# MD070B_POWER_AND_CONNECTORS.net
KiCad netlist of a schematic drawn in Altium Designer
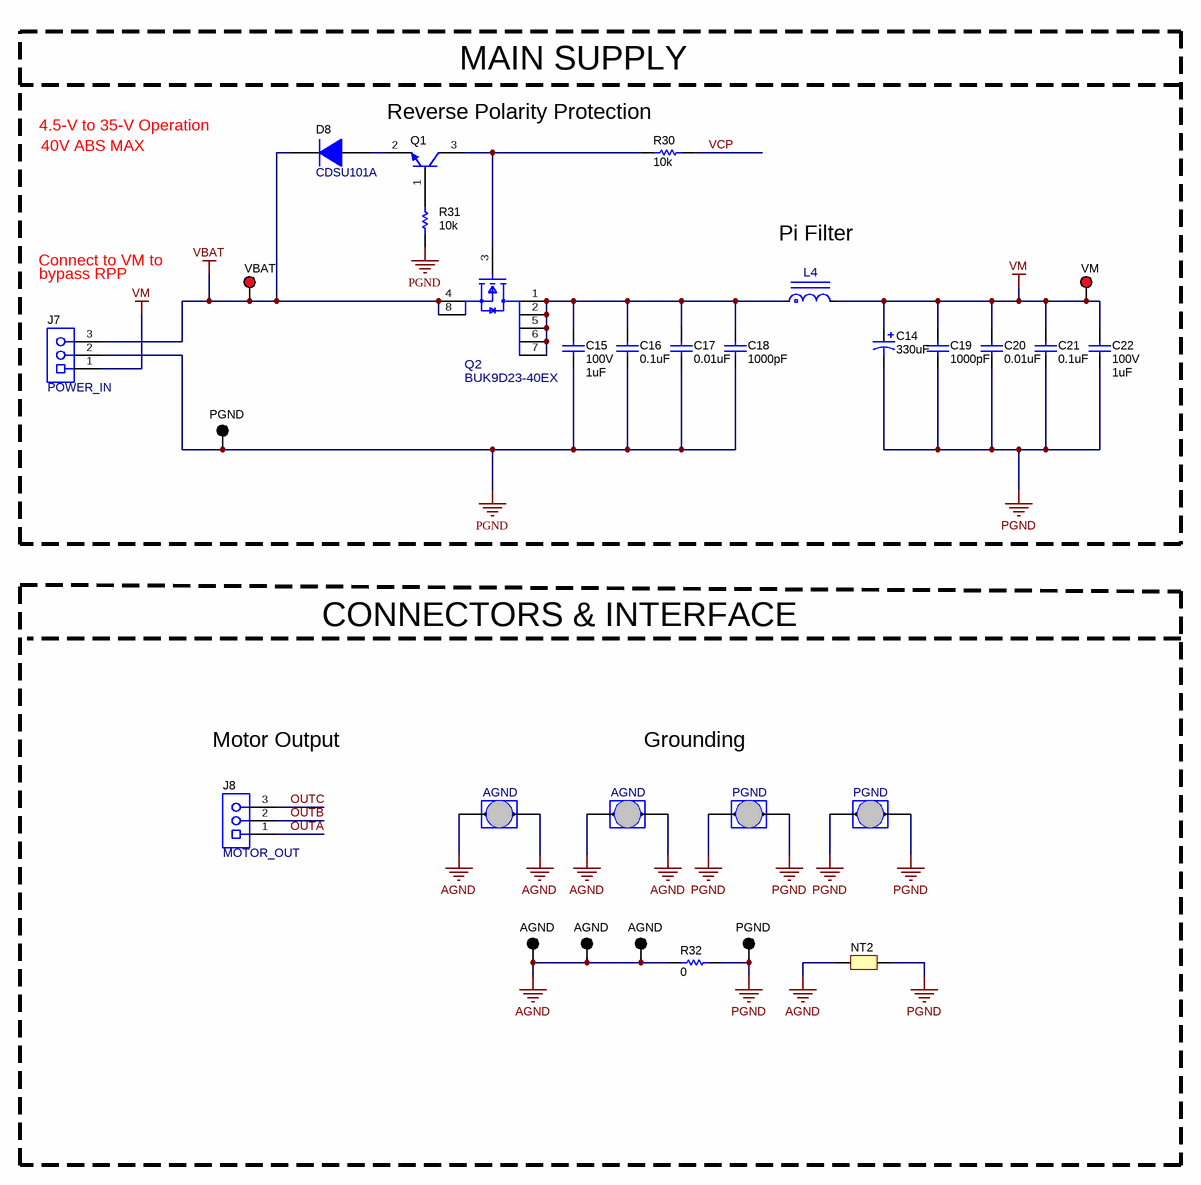
[diagram p0: MD070B_POWER_AND_CONNECTORS.SchDoc]

(export (version "E")
  (design (tool "Eeschema 10.0.6"))
  (components
    (comp (ref "C14")
      (value "ELXZ630ELL331MK20S")
      (footprint "Chemi-Con_1250x2000")
      (description "CAP, AL, 330 uF, 63 V, +/- 20%, AEC-Q200 Grade 2, TH")
      (fields
        (field (name "VALUEDISPLAYED") "330uF")
        (field (name "MANUFACTURER") "Chemi-Con")
        (field (name "PUBLISHER") "Texas Instruments")
      )
      (libsource (lib "Altium Vault - TI") (part "Cap_Polarized"))
    )
    (comp (ref "C15")
      (value "CL31B105KCHNNNE")
      (footprint "1206_180")
      (description "CAP, CERM, 1 uF, 100 V, +/- 10%, X7R, 1206")
      (fields
        (field (name "MANUFACTURER") "Samsung")
        (field (name "VDC_V") "100V")
        (field (name "VALUEDISPLAYED") "1uF")
        (field (name "PUBLISHER") "Texas Instruments")
      )
      (libsource (lib "Altium Vault - TI") (part "Capacitor"))
    )
    (comp (ref "C16")
      (value "CGA3E3X7S2A104K080AB")
      (footprint "0603L")
      (description "CAP, CERM, 0.1 uF, 100 V, +/- 10%, X7S, AEC-Q200 Grade 1, 0603")
      (fields
        (field (name "VALUEDISPLAYED") "0.1uF")
        (field (name "MANUFACTURER") "TDK")
        (field (name "PUBLISHER") "Texas Instruments")
      )
      (libsource (lib "Altium Vault - TI") (part "Capacitor"))
    )
    (comp (ref "C17")
      (value "CGA3E2X7R2A103K080AA")
      (footprint "0603L")
      (description "CAP, CERM, 0.01 uF, 100 V, +/- 10%, X7R, AEC-Q200 Grade 1, 0603")
      (fields
        (field (name "VALUEDISPLAYED") "0.01uF")
        (field (name "MANUFACTURER") "TDK")
        (field (name "PUBLISHER") "Texas Instruments")
      )
      (libsource (lib "Altium Vault - TI") (part "Capacitor"))
    )
    (comp (ref "C18")
      (value "CGA3E2X7R2A102K080AA")
      (footprint "0603L")
      (description "CAP, CERM, 1000 pF, 100 V, +/- 10%, X7R, AEC-Q200 Grade 1, 0603")
      (fields
        (field (name "VALUEDISPLAYED") "1000pF")
        (field (name "MANUFACTURER") "TDK")
        (field (name "PUBLISHER") "Texas Instruments")
      )
      (libsource (lib "Altium Vault - TI") (part "Capacitor"))
    )
    (comp (ref "C19")
      (value "CGA3E2X7R2A102K080AA")
      (footprint "0603L")
      (description "CAP, CERM, 1000 pF, 100 V, +/- 10%, X7R, AEC-Q200 Grade 1, 0603")
      (fields
        (field (name "VALUEDISPLAYED") "1000pF")
        (field (name "MANUFACTURER") "TDK")
        (field (name "PUBLISHER") "Texas Instruments")
      )
      (libsource (lib "Altium Vault - TI") (part "Capacitor"))
    )
    (comp (ref "C20")
      (value "CGA3E2X7R2A103K080AA")
      (footprint "0603L")
      (description "CAP, CERM, 0.01 uF, 100 V, +/- 10%, X7R, AEC-Q200 Grade 1, 0603")
      (fields
        (field (name "VALUEDISPLAYED") "0.01uF")
        (field (name "MANUFACTURER") "TDK")
        (field (name "PUBLISHER") "Texas Instruments")
      )
      (libsource (lib "Altium Vault - TI") (part "Capacitor"))
    )
    (comp (ref "C21")
      (value "CGA3E3X7S2A104K080AB")
      (footprint "0603L")
      (description "CAP, CERM, 0.1 uF, 100 V, +/- 10%, X7S, AEC-Q200 Grade 1, 0603")
      (fields
        (field (name "VALUEDISPLAYED") "0.1uF")
        (field (name "MANUFACTURER") "TDK")
        (field (name "PUBLISHER") "Texas Instruments")
      )
      (libsource (lib "Altium Vault - TI") (part "Capacitor"))
    )
    (comp (ref "C22")
      (value "CL31B105KCHNNNE")
      (footprint "1206_180")
      (description "CAP, CERM, 1 uF, 100 V, +/- 10%, X7R, 1206")
      (fields
        (field (name "MANUFACTURER") "Samsung")
        (field (name "VDC_V") "100V")
        (field (name "VALUEDISPLAYED") "1uF")
        (field (name "PUBLISHER") "Texas Instruments")
      )
      (libsource (lib "Altium Vault - TI") (part "Capacitor"))
    )
    (comp (ref "D8")
      (value "CDSU101A")
      (footprint "SOD-523F")
      (description "Diode, Switching, 90 V, 0.1 A, SOD-523F")
      (fields (field (name "MANUFACTURER") "Comchip Technology"))
      (libsource (lib "Altium Vault - TI") (part "DIODE"))
    )
    (comp (ref "J7")
      (value "POWER_IN")
      (footprint "On-Shore_ED120_3DS")
      (description "Terminal Block, 5.08 mm, 3x1, Brass, TH")
      (fields
        (field (name "MANUFACTURER") "On-Shore Technology")
        (field (name "PARTNUMBER") "ED120/3DS")
        (field (name "PUBLISHER") "Texas Instruments")
      )
      (libsource (lib "Altium Vault - TI") (part "Receptacle_3x1"))
    )
    (comp (ref "J8")
      (value "MOTOR_OUT")
      (footprint "On-Shore_ED120_3DS")
      (description "Terminal Block, 5.08 mm, 3x1, Brass, TH")
      (fields
        (field (name "MANUFACTURER") "On-Shore Technology")
        (field (name "PARTNUMBER") "ED120/3DS")
        (field (name "PUBLISHER") "Texas Instruments")
      )
      (libsource (lib "Altium Vault - TI") (part "Receptacle_3x1"))
    )
    (comp (ref "L4")
      (value "HCM1A1104V2-1R0-R")
      (footprint "FP-HCM1A1104V2-1R0-R_SMD2-MFG")
      (description "1 µH Shielded - Inductor 19 A 3.1mOhm Max Nonstandard")
      (fields
        (field (name "MANUFACTURER") "Eaton")
        (field (name "DIGIKEY PART NUMBER") "283-HCM1A1104V2-1R0-RCT-ND")
      )
      (libsource (lib "Altium Vault - TI") (part "SYM-HCM1A1104V2-1R0-R"))
    )
    (comp (ref "NT2")
      (value "Net-Tie")
      (footprint "Net-Tie_50milWide_30milLong")
      (description "Single point connection between nets.")
      (libsource (lib "Altium Vault - TI") (part "Net-Tie"))
    )
    (comp (ref "Q1")
      (value "FMMT620TA")
      (footprint "SOT-23L")
      (description "Transistor, NPN, 80 V, 1.5 A, AEC-Q101, SOT-23")
      (fields (field (name "MANUFACTURER") "Diodes Inc.") (field (name "PUBLISHER") "Texas Instruments"))
      (libsource (lib "Altium Vault - TI") (part "BJT_NPN_C3B1E2"))
    )
    (comp (ref "Q2")
      (value "BUK9D23-40EX")
      (footprint "FP-BUK9D23-40EX_SOT1220-MFG")
      (description "N-Channel 40V 8A (Ta) 15W (Tc) Surface Mount DFN2020MD-6")
      (fields
        (field (name "MOUSER PART NUMBER") "771-BUK9D23-40EX")
        (field (name "DIGIKEY PART NUMBER") "1727-7413-1-ND")
      )
      (libsource (lib "Altium Vault - TI") (part "SYM-BUK9D23-40EX"))
    )
    (comp (ref "R30")
      (value "10k")
      (footprint "0603L")
      (description "RES, 10 k, 5%, 0.1 W, AEC-Q200 Grade 0, 0603")
      (fields (field (name "PARTNUMBER") "CRCW060310K0JNEA") (field (name "MANUFACTURER") "Vishay-Dale"))
      (libsource (lib "Altium Vault - TI") (part "Resistor"))
    )
    (comp (ref "R31")
      (value "10k")
      (footprint "0603L")
      (description "RES, 10 k, 5%, 0.1 W, AEC-Q200 Grade 0, 0603")
      (fields (field (name "PARTNUMBER") "CRCW060310K0JNEA") (field (name "MANUFACTURER") "Vishay-Dale"))
      (libsource (lib "Altium Vault - TI") (part "Resistor"))
    )
    (comp (ref "R32")
      (value "RCA12060000ZSEA")
      (footprint "1206L")
      (description "RES, 0, 5%, 0.25 W, AEC-Q200 Grade 0, 1206")
      (fields
        (field (name "MANUFACTURER") "Vishay-Dale")
        (field (name "VALUEDISPLAYED") "0")
        (field (name "PUBLISHER") "Texas Instruments")
      )
      (libsource (lib "Altium Vault - TI") (part "Resistor"))
    )
    (comp (ref "TP23")
      (value "VBAT")
      (footprint "Keystone5005")
      (description "Test Point, Compact, Red, TH")
      (fields
        (field (name "PARTNUMBER") "5005")
        (field (name "MANUFACTURER") "Keystone")
        (field (name "PUBLISHER") "Texas Instruments")
      )
      (libsource (lib "Altium Vault - TI") (part "5005"))
    )
    (comp (ref "TP24")
      (value "VM")
      (footprint "Keystone5005")
      (description "Test Point, Compact, Red, TH")
      (fields
        (field (name "PARTNUMBER") "5005")
        (field (name "MANUFACTURER") "Keystone")
        (field (name "PUBLISHER") "Texas Instruments")
      )
      (libsource (lib "Altium Vault - TI") (part "5005"))
    )
    (comp (ref "TP25")
      (value "PGND")
      (footprint "Keystone5001")
      (description "Test Point, Miniature, Black, TH")
      (fields
        (field (name "MANUFACTURER") "Keystone")
        (field (name "PARTNUMBER") "5001")
        (field (name "PUBLISHER") "Texas Instruments")
      )
      (libsource (lib "Altium Vault - TI") (part "5001"))
    )
    (comp (ref "TP26")
      (value "AGND")
      (footprint "Harwin_D3082-05")
      (description "1mm Uninsulated Shorting Plug, 10.16mm spacing, TH")
      (fields
        (field (name "MANUFACTURER") "Harwin")
        (field (name "PARTNUMBER") "D3082-05")
        (field (name "PUBLISHER") "Texas Instruments")
      )
      (libsource (lib "Altium Vault - TI") (part "Jumper_2p"))
    )
    (comp (ref "TP27")
      (value "AGND")
      (footprint "Harwin_D3082-05")
      (description "1mm Uninsulated Shorting Plug, 10.16mm spacing, TH")
      (fields
        (field (name "MANUFACTURER") "Harwin")
        (field (name "PARTNUMBER") "D3082-05")
        (field (name "PUBLISHER") "Texas Instruments")
      )
      (libsource (lib "Altium Vault - TI") (part "Jumper_2p"))
    )
    (comp (ref "TP28")
      (value "PGND")
      (footprint "Harwin_D3082-05")
      (description "1mm Uninsulated Shorting Plug, 10.16mm spacing, TH")
      (fields
        (field (name "MANUFACTURER") "Harwin")
        (field (name "PARTNUMBER") "D3082-05")
        (field (name "PUBLISHER") "Texas Instruments")
      )
      (libsource (lib "Altium Vault - TI") (part "Jumper_2p"))
    )
    (comp (ref "TP29")
      (value "PGND")
      (footprint "Harwin_D3082-05")
      (description "1mm Uninsulated Shorting Plug, 10.16mm spacing, TH")
      (fields
        (field (name "MANUFACTURER") "Harwin")
        (field (name "PARTNUMBER") "D3082-05")
        (field (name "PUBLISHER") "Texas Instruments")
      )
      (libsource (lib "Altium Vault - TI") (part "Jumper_2p"))
    )
    (comp (ref "TP30")
      (value "AGND")
      (footprint "Keystone5001")
      (description "Test Point, Miniature, Black, TH")
      (fields
        (field (name "MANUFACTURER") "Keystone")
        (field (name "PARTNUMBER") "5001")
        (field (name "PUBLISHER") "Texas Instruments")
      )
      (libsource (lib "Altium Vault - TI") (part "5001"))
    )
    (comp (ref "TP31")
      (value "AGND")
      (footprint "Keystone5001")
      (description "Test Point, Miniature, Black, TH")
      (fields
        (field (name "MANUFACTURER") "Keystone")
        (field (name "PARTNUMBER") "5001")
        (field (name "PUBLISHER") "Texas Instruments")
      )
      (libsource (lib "Altium Vault - TI") (part "5001"))
    )
    (comp (ref "TP32")
      (value "AGND")
      (footprint "Keystone5001")
      (description "Test Point, Miniature, Black, TH")
      (fields
        (field (name "MANUFACTURER") "Keystone")
        (field (name "PARTNUMBER") "5001")
        (field (name "PUBLISHER") "Texas Instruments")
      )
      (libsource (lib "Altium Vault - TI") (part "5001"))
    )
    (comp (ref "TP33")
      (value "PGND")
      (footprint "Keystone5001")
      (description "Test Point, Miniature, Black, TH")
      (fields
        (field (name "MANUFACTURER") "Keystone")
        (field (name "PARTNUMBER") "5001")
        (field (name "PUBLISHER") "Texas Instruments")
      )
      (libsource (lib "Altium Vault - TI") (part "5001"))
    )
  )
  (nets
    (net (code "1") (name "/OUTA") (class "Default")
      (node (ref "J8") (pin "1") (pinfunction "1_1") (pintype "passive"))
    )
    (net (code "2") (name "/OUTB") (class "Default")
      (node (ref "J8") (pin "2") (pinfunction "2_2") (pintype "passive"))
    )
    (net (code "3") (name "/OUTC") (class "Default")
      (node (ref "J8") (pin "3") (pinfunction "3_3") (pintype "passive"))
    )
    (net (code "4") (name "/VCP") (class "Default")
      (node (ref "R30") (pin "1") (pinfunction "1_1") (pintype "passive"))
    )
    (net (code "5") (name "AGND") (class "Default")
      (node (ref "NT2") (pin "1") (pinfunction "1_1") (pintype "passive"))
      (node (ref "R32") (pin "1") (pinfunction "1_1") (pintype "passive"))
      (node (ref "TP26") (pin "1") (pinfunction "1_1") (pintype "passive"))
      (node (ref "TP26") (pin "2") (pinfunction "2_2") (pintype "passive"))
      (node (ref "TP27") (pin "1") (pinfunction "1_1") (pintype "passive"))
      (node (ref "TP27") (pin "2") (pinfunction "2_2") (pintype "passive"))
      (node (ref "TP30") (pin "1") (pintype "passive"))
      (node (ref "TP31") (pin "1") (pintype "passive"))
      (node (ref "TP32") (pin "1") (pintype "passive"))
    )
    (net (code "6") (name "Net-(C15-Pad1)") (class "Default")
      (node (ref "C15") (pin "1") (pinfunction "1_1") (pintype "passive"))
      (node (ref "C16") (pin "1") (pinfunction "1_1") (pintype "passive"))
      (node (ref "C17") (pin "1") (pinfunction "1_1") (pintype "passive"))
      (node (ref "C18") (pin "1") (pinfunction "1_1") (pintype "passive"))
      (node (ref "L4") (pin "1") (pinfunction "1_1") (pintype "passive"))
      (node (ref "Q2") (pin "1") (pinfunction "D_1") (pintype "passive"))
      (node (ref "Q2") (pin "2") (pinfunction "D_2") (pintype "passive"))
      (node (ref "Q2") (pin "5") (pinfunction "D_5") (pintype "passive"))
      (node (ref "Q2") (pin "6") (pinfunction "D_6") (pintype "passive"))
      (node (ref "Q2") (pin "7") (pinfunction "D_7") (pintype "passive"))
    )
    (net (code "7") (name "Net-(D8-A)") (class "Default")
      (node (ref "D8") (pin "2") (pinfunction "A_2") (pintype "passive"))
      (node (ref "Q1") (pin "2") (pinfunction "E_2") (pintype "passive"))
    )
    (net (code "8") (name "Net-(Q1-B)") (class "Default")
      (node (ref "Q1") (pin "1") (pinfunction "B_1") (pintype "passive"))
      (node (ref "R31") (pin "1") (pinfunction "1_1") (pintype "passive"))
    )
    (net (code "9") (name "Net-(Q1-C)") (class "Default")
      (node (ref "Q1") (pin "3") (pinfunction "C_3") (pintype "passive"))
      (node (ref "Q2") (pin "3") (pinfunction "G_3") (pintype "passive"))
      (node (ref "R30") (pin "2") (pinfunction "2_2") (pintype "passive"))
    )
    (net (code "10") (name "PGND") (class "Default")
      (node (ref "C14") (pin "2") (pinfunction "-_2") (pintype "passive"))
      (node (ref "C15") (pin "2") (pinfunction "2_2") (pintype "passive"))
      (node (ref "C16") (pin "2") (pinfunction "2_2") (pintype "passive"))
      (node (ref "C17") (pin "2") (pinfunction "2_2") (pintype "passive"))
      (node (ref "C18") (pin "2") (pinfunction "2_2") (pintype "passive"))
      (node (ref "C19") (pin "2") (pinfunction "2_2") (pintype "passive"))
      (node (ref "C20") (pin "2") (pinfunction "2_2") (pintype "passive"))
      (node (ref "C21") (pin "2") (pinfunction "2_2") (pintype "passive"))
      (node (ref "C22") (pin "2") (pinfunction "2_2") (pintype "passive"))
      (node (ref "J7") (pin "2") (pinfunction "2_2") (pintype "passive"))
      (node (ref "NT2") (pin "2") (pinfunction "2_2") (pintype "passive"))
      (node (ref "R31") (pin "2") (pinfunction "2_2") (pintype "passive"))
      (node (ref "R32") (pin "2") (pinfunction "2_2") (pintype "passive"))
      (node (ref "TP25") (pin "1") (pintype "passive"))
      (node (ref "TP28") (pin "1") (pinfunction "1_1") (pintype "passive"))
      (node (ref "TP28") (pin "2") (pinfunction "2_2") (pintype "passive"))
      (node (ref "TP29") (pin "1") (pinfunction "1_1") (pintype "passive"))
      (node (ref "TP29") (pin "2") (pinfunction "2_2") (pintype "passive"))
      (node (ref "TP33") (pin "1") (pintype "passive"))
    )
    (net (code "11") (name "VBAT") (class "Default")
      (node (ref "D8") (pin "1") (pinfunction "K_1") (pintype "passive"))
      (node (ref "J7") (pin "3") (pinfunction "3_3") (pintype "passive"))
      (node (ref "Q2") (pin "4") (pinfunction "S_4") (pintype "passive"))
      (node (ref "Q2") (pin "8") (pinfunction "S_8") (pintype "passive"))
      (node (ref "TP23") (pin "1") (pintype "passive"))
    )
    (net (code "12") (name "VM") (class "Default")
      (node (ref "C14") (pin "1") (pinfunction "+_1") (pintype "passive"))
      (node (ref "C19") (pin "1") (pinfunction "1_1") (pintype "passive"))
      (node (ref "C20") (pin "1") (pinfunction "1_1") (pintype "passive"))
      (node (ref "C21") (pin "1") (pinfunction "1_1") (pintype "passive"))
      (node (ref "C22") (pin "1") (pinfunction "1_1") (pintype "passive"))
      (node (ref "J7") (pin "1") (pinfunction "1_1") (pintype "passive"))
      (node (ref "L4") (pin "2") (pinfunction "2_2") (pintype "passive"))
      (node (ref "TP24") (pin "1") (pintype "passive"))
    )
  )
)
